# design.net
KiCad netlist of a schematic drawn in Altium Designer
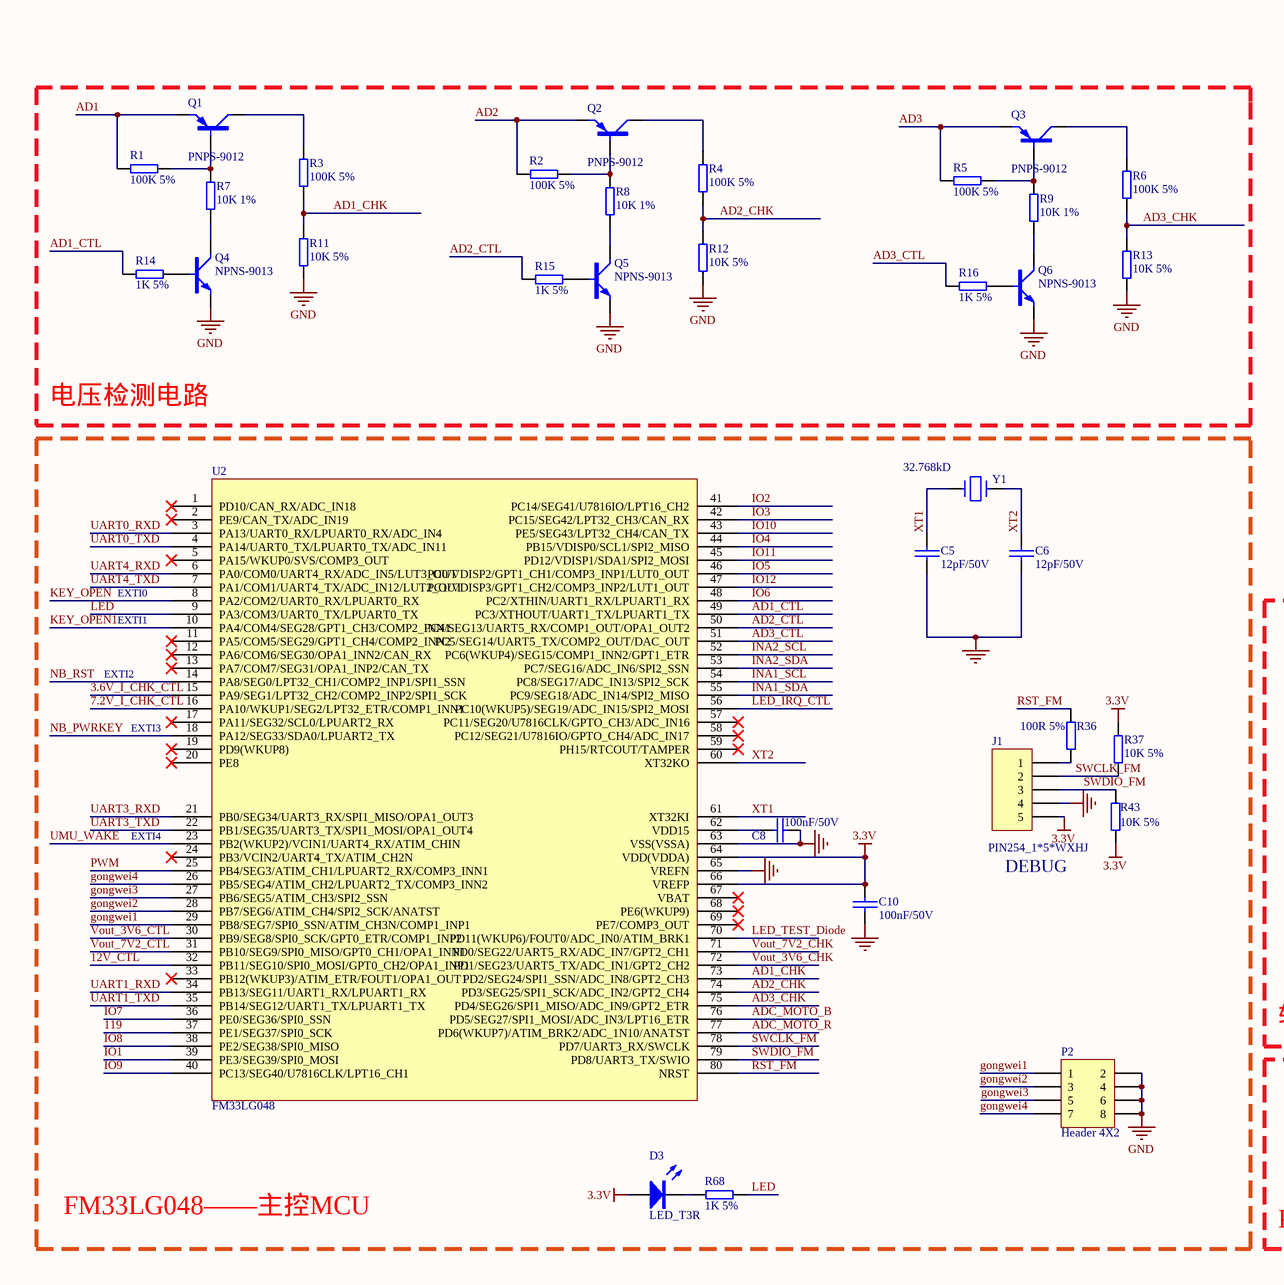
[diagram p0: 主控.SchDoc, left]
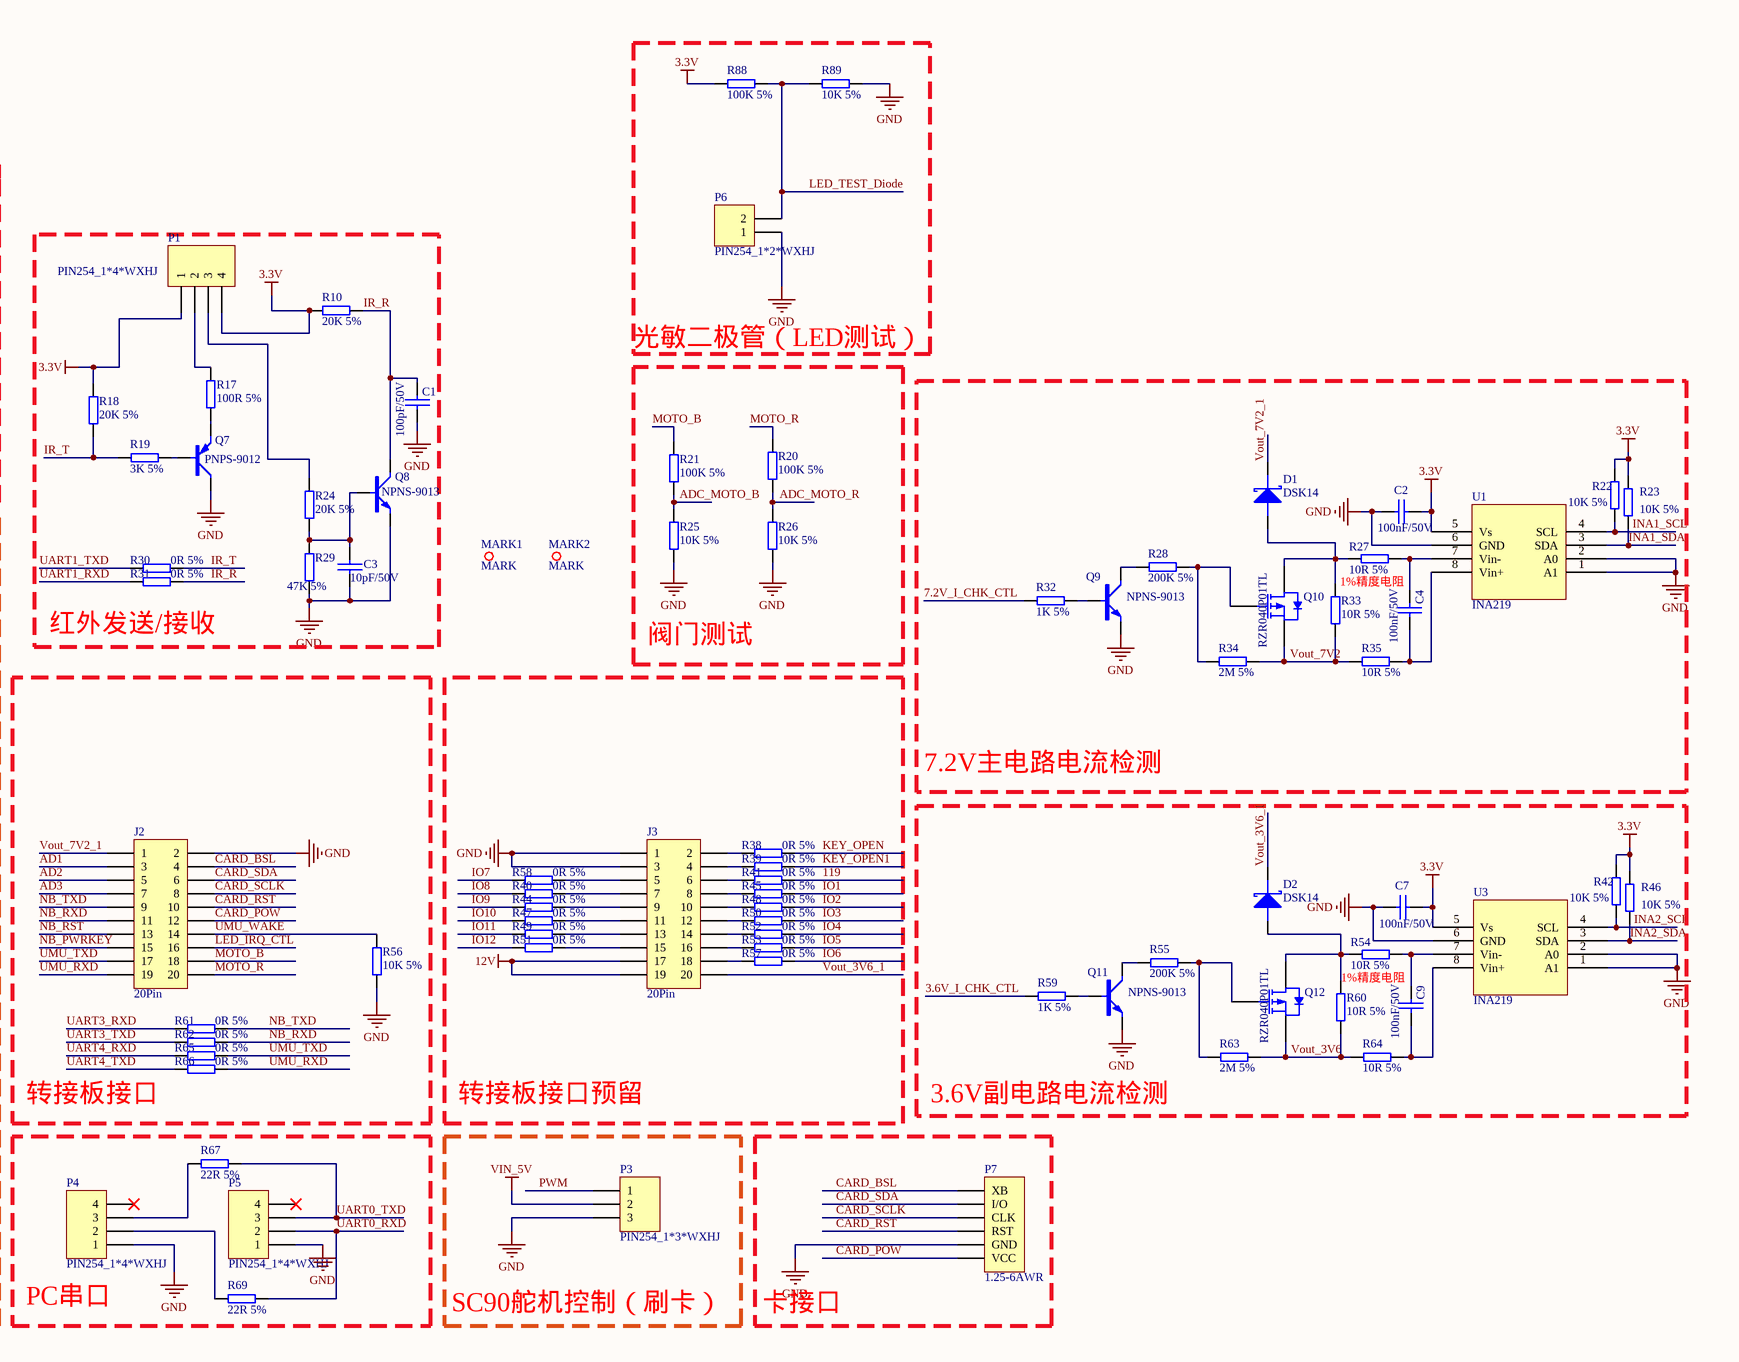
[diagram p1: 主控.SchDoc, right]

(export (version "E")
  (design (tool "Eeschema 10.0.6"))
  (components
    (comp (ref "C1")
      (value "100pF/50V")
      (footprint "CAP0603")
      (description "101pf,50 V,±5%,0603,国巨,CC0603JRNP09BN101")
      (fields (field (name "PART NUMBER") "101020103-0010"))
      (libsource (lib "Database_Libs2") (part "CC03JPO9_101P"))
    )
    (comp (ref "C2")
      (value "100nF/50V")
      (footprint "CAP0603")
      (description "104pF,50 V,±10%,0603,国巨,CC0603KRX7R9BB104")
      (fields (field (name "PART NUMBER") "101020103-0021"))
      (libsource (lib "Database_Libs2") (part "CC03K7R9_100N"))
    )
    (comp (ref "C3")
      (value "10pF/50V")
      (footprint "CAP0603")
      (description "10pF,50 V,±5%,0603,X7R,国巨,CC0603JRNPO9BN100")
      (fields (field (name "PART NUMBER") "101020103-0014"))
      (libsource (lib "Database_Libs2") (part "CC03JPO9_10P"))
    )
    (comp (ref "C4")
      (value "100nF/50V")
      (footprint "CAP0603")
      (description "104pF,50 V,±10%,0603,国巨,CC0603KRX7R9BB104")
      (fields (field (name "PART NUMBER") "101020103-0021"))
      (libsource (lib "Database_Libs2") (part "CC03K7R9_100N"))
    )
    (comp (ref "C5")
      (value "12pF/50V")
      (footprint "CAP0603")
      (description "12P,50 V,±5%,0603,国巨,CC0603JRNPO9BN12")
      (fields (field (name "PART NUMBER") "101020103-0005"))
      (libsource (lib "Database_Libs2") (part "CC03JPO9_12P"))
    )
    (comp (ref "C6")
      (value "12pF/50V")
      (footprint "CAP0603")
      (description "12P,50 V,±5%,0603,国巨,CC0603JRNPO9BN12")
      (fields (field (name "PART NUMBER") "101020103-0005"))
      (libsource (lib "Database_Libs2") (part "CC03JPO9_12P"))
    )
    (comp (ref "C7")
      (value "100nF/50V")
      (footprint "CAP0603")
      (description "104pF,50 V,±10%,0603,国巨,CC0603KRX7R9BB104")
      (fields (field (name "PART NUMBER") "101020103-0021"))
      (libsource (lib "Database_Libs2") (part "CC03K7R9_100N"))
    )
    (comp (ref "C8")
      (value "100nF/50V")
      (footprint "CAP0603")
      (description "104pF,50 V,±10%,0603,国巨,CC0603KRX7R9BB104")
      (fields (field (name "PART NUMBER") "101020103-0021"))
      (libsource (lib "Database_Libs2") (part "CC03K7R9_100N"))
    )
    (comp (ref "C9")
      (value "100nF/50V")
      (footprint "CAP0603")
      (description "104pF,50 V,±10%,0603,国巨,CC0603KRX7R9BB104")
      (fields (field (name "PART NUMBER") "101020103-0021"))
      (libsource (lib "Database_Libs2") (part "CC03K7R9_100N"))
    )
    (comp (ref "C10")
      (value "100nF/50V")
      (footprint "CAP0603")
      (description "104pF,50 V,±10%,0603,国巨,CC0603KRX7R9BB104")
      (fields (field (name "PART NUMBER") "101020103-0021"))
      (libsource (lib "Database_Libs2") (part "CC03K7R9_100N"))
    )
    (comp (ref "D1")
      (value "DSK14")
      (footprint "SOD-123FL")
      (description "DSK14,SOD-123FL,1 A,40 V,28 V,台湾强茂集团苏州群鑫电子,DSK14")
      (fields (field (name "PART NUMBER") "101040101-0043"))
      (libsource (lib "Database_Libs2") (part "02_DSK14"))
    )
    (comp (ref "D2")
      (value "DSK14")
      (footprint "SOD-123FL")
      (description "DSK14,SOD-123FL,1 A,40 V,28 V,台湾强茂集团苏州群鑫电子,DSK14")
      (fields (field (name "PART NUMBER") "101040101-0043"))
      (libsource (lib "Database_Libs2") (part "02_DSK14"))
    )
    (comp (ref "D3")
      (value "LED_T3R")
      (footprint "LED2_300")
      (description "圆形插件,3mm 圆形,插件,红光,湖北匡通电子有限公司,3BB4HC")
      (fields (field (name "PART NUMBER") "101040102-0001"))
      (libsource (lib "Database_Libs2") (part "01-LED_T3R"))
    )
    (comp (ref "J1")
      (value "PIN254_1*5*WXHJ")
      (footprint "PIN254_1*5*1100S")
      (description "1*5 ，Φ1.0 ，2.54mm，直脚,无需焊接器件")
      (fields (field (name "PART NUMBER") "AD_WXHJ_PinHeader_02"))
      (libsource (lib "Database_Libs2") (part "PIN254_1*5*1100S"))
    )
    (comp (ref "J2")
      (value "20Pin")
      (footprint "DC254_2*10")
      (description "DC2 2.54mm 2x10pin,2.54mm间距，2x10pin，32×8.55×27.5mm,母头,双排,双排牛角座")
      (fields (field (name "PART NUMBER") "1010902-0139"))
      (libsource (lib "转接板封装") (part "20Pin"))
    )
    (comp (ref "J3")
      (value "20Pin")
      (footprint "DC254_2*10")
      (description "DC2 2.54mm 2x10pin,2.54mm间距，2x10pin，32×8.55×27.5mm,母头,双排,双排牛角座")
      (fields (field (name "PART NUMBER") "1010902-0139"))
      (libsource (lib "转接板封装") (part "20Pin"))
    )
    (comp (ref "MARK1")
      (value "MARK")
      (footprint "MARK")
      (description "MARK点")
      (fields (field (name "PART NUMBER") "AD_WXHJ_MARK_01"))
      (libsource (lib "转接板封装") (part "MARK"))
    )
    (comp (ref "MARK2")
      (value "MARK")
      (footprint "MARK")
      (description "MARK点")
      (fields (field (name "PART NUMBER") "AD_WXHJ_MARK_01"))
      (libsource (lib "转接板封装") (part "MARK"))
    )
    (comp (ref "P1")
      (value "PIN254_1*4*WXHJ")
      (footprint "PIN254_1*4*1100S")
      (description "1*4 ，Φ1.0 ，2.54mm，直脚,无需焊接器件")
      (fields (field (name "PART NUMBER") "AD_WXHJ_PinHeader_01"))
      (libsource (lib "") (part "PIN254_1*4*1100S_1"))
    )
    (comp (ref "P2")
      (value "Header 4X2")
      (footprint "HDR2X4")
      (description "Header, 4-Pin, Dual row")
      (libsource (lib "CBB_Lib_SCH") (part "Header 4X2"))
    )
    (comp (ref "P3")
      (value "PIN254_1*3*WXHJ")
      (footprint "PIN254_1*3*1100S")
      (description "1*3 ，Φ1.0 ，2.54mm，直脚,无需焊接器件")
      (fields (field (name "PART NUMBER") "AD_WXHJ_PinHeader_01"))
      (libsource (lib "模拟计量") (part "PIN254_1*3*1100S"))
    )
    (comp (ref "P4")
      (value "PIN254_1*4*WXHJ")
      (footprint "PIN254_1*4*1100S")
      (description "1*4 ，Φ1.0 ，2.54mm，直脚,无需焊接器件")
      (fields (field (name "PART NUMBER") "AD_WXHJ_PinHeader_01"))
      (libsource (lib "Database_Libs2") (part "PIN254_1*4*1100S"))
    )
    (comp (ref "P5")
      (value "PIN254_1*4*WXHJ")
      (footprint "PIN254_1*4*1100S")
      (description "1*4 ，Φ1.0 ，2.54mm，直脚,无需焊接器件")
      (fields (field (name "PART NUMBER") "AD_WXHJ_PinHeader_01"))
      (libsource (lib "Database_Libs2") (part "PIN254_1*4*1100S"))
    )
    (comp (ref "P6")
      (value "PIN254_1*2*WXHJ")
      (footprint "PIN254_1*2*1100S")
      (description "1*2 ，Φ1.0 ，2.54mm，直脚,无需焊接器件")
      (fields (field (name "PART NUMBER") "AD_WXHJ_PinHeader_01"))
      (libsource (lib "转接板封装") (part "PIN254_1*2*1100S"))
    )
    (comp (ref "P7")
      (value "1.25-6AWR")
      (footprint "SMT-1.25-6")
      (description "1.25-6AWR 卷,6针1.25mm,母头,单排,贴片卧式")
      (fields (field (name "PART NUMBER") "1010902-0121"))
      (libsource (lib "Database_Libs2") (part "CARD1608"))
    )
    (comp (ref "Q1")
      (value "PNPS-9012")
      (footprint "SOT-23")
      (description "9012,PNP,SOT-23,JCET;长电,S9012")
      (fields (field (name "PART NUMBER") "101040201-0001"))
      (libsource (lib "Database_Libs2") (part "03_PNPS-9012"))
    )
    (comp (ref "Q2")
      (value "PNPS-9012")
      (footprint "SOT-23")
      (description "9012,PNP,SOT-23,JCET;长电,S9012")
      (fields (field (name "PART NUMBER") "101040201-0001"))
      (libsource (lib "Database_Libs2") (part "03_PNPS-9012"))
    )
    (comp (ref "Q3")
      (value "PNPS-9012")
      (footprint "SOT-23")
      (description "9012,PNP,SOT-23,JCET;长电,S9012")
      (fields (field (name "PART NUMBER") "101040201-0001"))
      (libsource (lib "Database_Libs2") (part "03_PNPS-9012"))
    )
    (comp (ref "Q4")
      (value "NPNS-9013")
      (footprint "SOT-23")
      (description "9013,NPN,SOT-23,长电,S9013")
      (fields (field (name "PART NUMBER") "101040201-0002"))
      (libsource (lib "Database_Libs2") (part "03_NPNS-9013"))
    )
    (comp (ref "Q5")
      (value "NPNS-9013")
      (footprint "SOT-23")
      (description "9013,NPN,SOT-23,长电,S9013")
      (fields (field (name "PART NUMBER") "101040201-0002"))
      (libsource (lib "Database_Libs2") (part "03_NPNS-9013"))
    )
    (comp (ref "Q6")
      (value "NPNS-9013")
      (footprint "SOT-23")
      (description "9013,NPN,SOT-23,长电,S9013")
      (fields (field (name "PART NUMBER") "101040201-0002"))
      (libsource (lib "Database_Libs2") (part "03_NPNS-9013"))
    )
    (comp (ref "Q7")
      (value "PNPS-9012")
      (footprint "SOT-23")
      (description "9012,PNP,SOT-23,JCET;长电,S9012")
      (fields (field (name "PART NUMBER") "101040201-0001"))
      (libsource (lib "Database_Libs2") (part "03_PNPS-9012"))
    )
    (comp (ref "Q8")
      (value "NPNS-9013")
      (footprint "SOT-23")
      (description "9013,NPN,SOT-23,长电,S9013")
      (fields (field (name "PART NUMBER") "101040201-0002"))
      (libsource (lib "Database_Libs2") (part "03_NPNS-9013"))
    )
    (comp (ref "Q9")
      (value "NPNS-9013")
      (footprint "SOT-23")
      (description "9013,NPN,SOT-23,长电,S9013")
      (fields (field (name "PART NUMBER") "101040201-0002"))
      (libsource (lib "Database_Libs2") (part "03_NPNS-9013"))
    )
    (comp (ref "Q10")
      (value "RZR040P01TL")
      (footprint "SOT-23")
      (description "RZR040P01TL；1.5v导通,P-MOS,SOT-23,罗姆,RZR040P01TL")
      (fields (field (name "PART NUMBER") "101040201-0010"))
      (libsource (lib "Database_Libs2") (part "03_P-RZR040P01TL"))
    )
    (comp (ref "Q11")
      (value "NPNS-9013")
      (footprint "SOT-23")
      (description "9013,NPN,SOT-23,长电,S9013")
      (fields (field (name "PART NUMBER") "101040201-0002"))
      (libsource (lib "Database_Libs2") (part "03_NPNS-9013"))
    )
    (comp (ref "Q12")
      (value "RZR040P01TL")
      (footprint "SOT-23")
      (description "RZR040P01TL；1.5v导通,P-MOS,SOT-23,罗姆,RZR040P01TL")
      (fields (field (name "PART NUMBER") "101040201-0010"))
      (libsource (lib "Database_Libs2") (part "03_P-RZR040P01TL"))
    )
    (comp (ref "R1")
      (value "100K 5%")
      (footprint "RES0603")
      (description "国巨,±5%,0603,,155 ℃,-55 ℃,RC0603JR-07100KL,无铅,100 ppm/℃,1/10W,,100K")
      (fields (field (name "PART NUMBER") "101010103-0005"))
      (libsource (lib "Database_Libs2") (part "RC03J_100K"))
    )
    (comp (ref "R2")
      (value "100K 5%")
      (footprint "RES0603")
      (description "国巨,±5%,0603,,155 ℃,-55 ℃,RC0603JR-07100KL,无铅,100 ppm/℃,1/10W,,100K")
      (fields (field (name "PART NUMBER") "101010103-0005"))
      (libsource (lib "Database_Libs2") (part "RC03J_100K"))
    )
    (comp (ref "R3")
      (value "100K 5%")
      (footprint "RES0603")
      (description "国巨,±5%,0603,,155 ℃,-55 ℃,RC0603JR-07100KL,无铅,100 ppm/℃,1/10W,,100K")
      (fields (field (name "PART NUMBER") "101010103-0005"))
      (libsource (lib "Database_Libs2") (part "RC03J_100K"))
    )
    (comp (ref "R4")
      (value "100K 5%")
      (footprint "RES0603")
      (description "国巨,±5%,0603,,155 ℃,-55 ℃,RC0603JR-07100KL,无铅,100 ppm/℃,1/10W,,100K")
      (fields (field (name "PART NUMBER") "101010103-0005"))
      (libsource (lib "Database_Libs2") (part "RC03J_100K"))
    )
    (comp (ref "R5")
      (value "100K 5%")
      (footprint "RES0603")
      (description "国巨,±5%,0603,,155 ℃,-55 ℃,RC0603JR-07100KL,无铅,100 ppm/℃,1/10W,,100K")
      (fields (field (name "PART NUMBER") "101010103-0005"))
      (libsource (lib "Database_Libs2") (part "RC03J_100K"))
    )
    (comp (ref "R6")
      (value "100K 5%")
      (footprint "RES0603")
      (description "国巨,±5%,0603,,155 ℃,-55 ℃,RC0603JR-07100KL,无铅,100 ppm/℃,1/10W,,100K")
      (fields (field (name "PART NUMBER") "101010103-0005"))
      (libsource (lib "Database_Libs2") (part "RC03J_100K"))
    )
    (comp (ref "R7")
      (value "10K 1%")
      (footprint "RES0603")
      (description "10K±1%,1/10W,0603")
      (fields (field (name "PART NUMBER") "101010103-0052"))
      (libsource (lib "Database_Libs2") (part "RC03J_10K"))
    )
    (comp (ref "R8")
      (value "10K 1%")
      (footprint "RES0603")
      (description "10K±1%,1/10W,0603")
      (fields (field (name "PART NUMBER") "101010103-0052"))
      (libsource (lib "Database_Libs2") (part "RC03J_10K"))
    )
    (comp (ref "R9")
      (value "10K 1%")
      (footprint "RES0603")
      (description "10K±1%,1/10W,0603")
      (fields (field (name "PART NUMBER") "101010103-0052"))
      (libsource (lib "Database_Libs2") (part "RC03J_10K"))
    )
    (comp (ref "R10")
      (value "20K 5%")
      (footprint "RES0603")
      (description "国巨,±5%,0603,,155 ℃,-55 ℃,RC0603JR-0720KL,无铅,200 ppm/℃,1/10W,,20K")
      (fields (field (name "PART NUMBER") "101010103-0004"))
      (libsource (lib "Database_Libs2") (part "RC03J_20K"))
    )
    (comp (ref "R11")
      (value "10K 5%")
      (footprint "RES0603")
      (description "国巨,±5%,0603,,155 ℃,-55 ℃,RC0603JR-0710KL,无铅,200 ppm/℃,1/10W,,10K")
      (fields (field (name "PART NUMBER") "101010103-0003"))
      (libsource (lib "Database_Libs2") (part "RC03J_10K"))
    )
    (comp (ref "R12")
      (value "10K 5%")
      (footprint "RES0603")
      (description "国巨,±5%,0603,,155 ℃,-55 ℃,RC0603JR-0710KL,无铅,200 ppm/℃,1/10W,,10K")
      (fields (field (name "PART NUMBER") "101010103-0003"))
      (libsource (lib "Database_Libs2") (part "RC03J_10K"))
    )
    (comp (ref "R13")
      (value "10K 5%")
      (footprint "RES0603")
      (description "国巨,±5%,0603,,155 ℃,-55 ℃,RC0603JR-0710KL,无铅,200 ppm/℃,1/10W,,10K")
      (fields (field (name "PART NUMBER") "101010103-0003"))
      (libsource (lib "Database_Libs2") (part "RC03J_10K"))
    )
    (comp (ref "R14")
      (value "1K 5%")
      (footprint "RES0603")
      (description "1K,±5%,1/10W,0603,国巨,RC0603JR-071KL")
      (fields (field (name "PART NUMBER") "101010103-0008"))
      (libsource (lib "Database_Libs2") (part "RC03J_1K"))
    )
    (comp (ref "R15")
      (value "1K 5%")
      (footprint "RES0603")
      (description "1K,±5%,1/10W,0603,国巨,RC0603JR-071KL")
      (fields (field (name "PART NUMBER") "101010103-0008"))
      (libsource (lib "Database_Libs2") (part "RC03J_1K"))
    )
    (comp (ref "R16")
      (value "1K 5%")
      (footprint "RES0603")
      (description "1K,±5%,1/10W,0603,国巨,RC0603JR-071KL")
      (fields (field (name "PART NUMBER") "101010103-0008"))
      (libsource (lib "Database_Libs2") (part "RC03J_1K"))
    )
    (comp (ref "R17")
      (value "100R 5%")
      (footprint "RES0603")
      (description "100R,±5%,1/10W,0603,国巨,RC0603JR-07100RL")
      (fields (field (name "PART NUMBER") "101010103-0022"))
      (libsource (lib "Database_Libs2") (part "RC03J_100R"))
    )
    (comp (ref "R18")
      (value "20K 5%")
      (footprint "RES0603")
      (description "国巨,±5%,0603,,155 ℃,-55 ℃,RC0603JR-0720KL,无铅,200 ppm/℃,1/10W,,20K")
      (fields (field (name "PART NUMBER") "101010103-0004"))
      (libsource (lib "Database_Libs2") (part "RC03J_20K"))
    )
    (comp (ref "R19")
      (value "3K 5%")
      (footprint "RES0603")
      (description "国巨,±5%,0603,,155 ℃,-55 ℃,RC0603JR-073KL,无铅,100 ppm/℃,1/10W,,3K")
      (fields (field (name "PART NUMBER") "101010103-0006"))
      (libsource (lib "Database_Libs2") (part "RC03J_3K"))
    )
    (comp (ref "R20")
      (value "100K 5%")
      (footprint "RES0603")
      (description "100K±5%,1/10W,0603")
      (fields (field (name "PART NUMBER") "101010103-0005"))
      (libsource (lib "Database_Libs1") (part "RC03JF_100K"))
    )
    (comp (ref "R21")
      (value "100K 5%")
      (footprint "RES0603")
      (description "100K±5%,1/10W,0603")
      (fields (field (name "PART NUMBER") "101010103-0005"))
      (libsource (lib "Database_Libs1") (part "RC03JF_100K"))
    )
    (comp (ref "R22")
      (value "10K 5%")
      (footprint "RES0603")
      (description "国巨,±5%,0603,,155 ℃,-55 ℃,RC0603JR-0710KL,无铅,200 ppm/℃,1/10W,,10K")
      (fields (field (name "PART NUMBER") "101010103-0003"))
      (libsource (lib "Database_Libs2") (part "RC03J_10K"))
    )
    (comp (ref "R23")
      (value "10K 5%")
      (footprint "RES0603")
      (description "国巨,±5%,0603,,155 ℃,-55 ℃,RC0603JR-0710KL,无铅,200 ppm/℃,1/10W,,10K")
      (fields (field (name "PART NUMBER") "101010103-0003"))
      (libsource (lib "Database_Libs2") (part "RC03J_10K"))
    )
    (comp (ref "R24")
      (value "20K 5%")
      (footprint "RES0603")
      (description "国巨,±5%,0603,,155 ℃,-55 ℃,RC0603JR-0720KL,无铅,200 ppm/℃,1/10W,,20K")
      (fields (field (name "PART NUMBER") "101010103-0004"))
      (libsource (lib "Database_Libs2") (part "RC03J_20K"))
    )
    (comp (ref "R25")
      (value "10K 5%")
      (footprint "RES0603")
      (description "国巨,±5%,0603,,155 ℃,-55 ℃,RC0603JR-0710KL,无铅,200 ppm/℃,1/10W,,10K")
      (fields (field (name "PART NUMBER") "101010103-0003"))
      (libsource (lib "Database_Libs2") (part "RC03J_10K"))
    )
    (comp (ref "R26")
      (value "10K 5%")
      (footprint "RES0603")
      (description "国巨,±5%,0603,,155 ℃,-55 ℃,RC0603JR-0710KL,无铅,200 ppm/℃,1/10W,,10K")
      (fields (field (name "PART NUMBER") "101010103-0003"))
      (libsource (lib "Database_Libs2") (part "RC03J_10K"))
    )
    (comp (ref "R27")
      (value "10R 5%")
      (footprint "RES0603")
      (description "10R,±5%,1/10W,0603,国巨,RC0603JR-0710RL")
      (fields (field (name "PART NUMBER") "101010103-0017"))
      (libsource (lib "Database_Libs2") (part "RC03J_10R"))
    )
    (comp (ref "R28")
      (value "200K 5%")
      (footprint "RES0603")
      (description "200K,±5%,1/10W,0603,国巨,RC0603JR-07200KL")
      (fields (field (name "PART NUMBER") "101010103-0034"))
      (libsource (lib "Database_Libs2") (part "RC03J_200K"))
    )
    (comp (ref "R29")
      (value "47K 5%")
      (footprint "RES0603")
      (description "47K,±5%,1/10W,0603,国巨,RC0603JR-0747KL")
      (fields (field (name "PART NUMBER") "101010103-0012"))
      (libsource (lib "Database_Libs2") (part "RC03J_47K"))
    )
    (comp (ref "R30")
      (value "0R 5%")
      (footprint "RES0603")
      (description "国巨,±5%,0603,,155 ℃,-55 ℃,RC0603J2-070RL,无铅,200 ppm/℃,1/10W,,0R")
      (fields (field (name "PART NUMBER") "101010103-0001"))
      (libsource (lib "Database_Libs2") (part "RC03J_0R"))
    )
    (comp (ref "R31")
      (value "0R 5%")
      (footprint "RES0603")
      (description "国巨,±5%,0603,,155 ℃,-55 ℃,RC0603J2-070RL,无铅,200 ppm/℃,1/10W,,0R")
      (fields (field (name "PART NUMBER") "101010103-0001"))
      (libsource (lib "Database_Libs2") (part "RC03J_0R"))
    )
    (comp (ref "R32")
      (value "1K 5%")
      (footprint "RES0603")
      (description "1K,±5%,1/10W,0603,国巨,RC0603JR-071KL")
      (fields (field (name "PART NUMBER") "101010103-0008"))
      (libsource (lib "Database_Libs2") (part "RC03J_1K"))
    )
    (comp (ref "R33")
      (value "10R 5%")
      (footprint "RES0603")
      (description "10R,±5%,1/10W,0603,国巨,RC0603JR-0710RL")
      (fields (field (name "PART NUMBER") "101010103-0017"))
      (libsource (lib "Database_Libs2") (part "RC03J_10R"))
    )
    (comp (ref "R34")
      (value "2M 5%")
      (footprint "RES0603")
      (description "国巨,±5%,0603,,155 ℃,-55 ℃,RC0603JR-072ML,含铅,100 ppm/℃,1/10W,,2M")
      (fields (field (name "PART NUMBER") "101010103-0025"))
      (libsource (lib "Database_Libs2") (part "RC03J_2M"))
    )
    (comp (ref "R35")
      (value "10R 5%")
      (footprint "RES0603")
      (description "10R,±5%,1/10W,0603,国巨,RC0603JR-0710RL")
      (fields (field (name "PART NUMBER") "101010103-0017"))
      (libsource (lib "Database_Libs2") (part "RC03J_10R"))
    )
    (comp (ref "R36")
      (value "100R 5%")
      (footprint "RES0603")
      (description "100R,±5%,1/10W,0603,国巨,RC0603JR-07100RL")
      (fields (field (name "PART NUMBER") "101010103-0022"))
      (libsource (lib "Database_Libs2") (part "RC03J_100R"))
    )
    (comp (ref "R37")
      (value "10K 5%")
      (footprint "RES0603")
      (description "国巨,±5%,0603,,155 ℃,-55 ℃,RC0603JR-0710KL,无铅,200 ppm/℃,1/10W,,10K")
      (fields (field (name "PART NUMBER") "101010103-0003"))
      (libsource (lib "Database_Libs2") (part "RC03J_10K"))
    )
    (comp (ref "R38")
      (value "0R 5%")
      (footprint "RES0603")
      (description "国巨,±5%,0603,,155 ℃,-55 ℃,RC0603J2-070RL,无铅,200 ppm/℃,1/10W,,0R")
      (fields (field (name "PART NUMBER") "101010103-0001"))
      (libsource (lib "Database_Libs2") (part "RC03J_0R"))
    )
    (comp (ref "R39")
      (value "0R 5%")
      (footprint "RES0603")
      (description "国巨,±5%,0603,,155 ℃,-55 ℃,RC0603J2-070RL,无铅,200 ppm/℃,1/10W,,0R")
      (fields (field (name "PART NUMBER") "101010103-0001"))
      (libsource (lib "Database_Libs2") (part "RC03J_0R"))
    )
    (comp (ref "R40")
      (value "0R 5%")
      (footprint "RES0603")
      (description "国巨,±5%,0603,,155 ℃,-55 ℃,RC0603J2-070RL,无铅,200 ppm/℃,1/10W,,0R")
      (fields (field (name "PART NUMBER") "101010103-0001"))
      (libsource (lib "Database_Libs2") (part "RC03J_0R"))
    )
    (comp (ref "R41")
      (value "0R 5%")
      (footprint "RES0603")
      (description "国巨,±5%,0603,,155 ℃,-55 ℃,RC0603J2-070RL,无铅,200 ppm/℃,1/10W,,0R")
      (fields (field (name "PART NUMBER") "101010103-0001"))
      (libsource (lib "Database_Libs2") (part "RC03J_0R"))
    )
    (comp (ref "R42")
      (value "10K 5%")
      (footprint "RES0603")
      (description "国巨,±5%,0603,,155 ℃,-55 ℃,RC0603JR-0710KL,无铅,200 ppm/℃,1/10W,,10K")
      (fields (field (name "PART NUMBER") "101010103-0003"))
      (libsource (lib "Database_Libs2") (part "RC03J_10K"))
    )
    (comp (ref "R43")
      (value "10K 5%")
      (footprint "RES0603")
      (description "国巨,±5%,0603,,155 ℃,-55 ℃,RC0603JR-0710KL,无铅,200 ppm/℃,1/10W,,10K")
      (fields (field (name "PART NUMBER") "101010103-0003"))
      (libsource (lib "Database_Libs2") (part "RC03J_10K"))
    )
    (comp (ref "R44")
      (value "0R 5%")
      (footprint "RES0603")
      (description "国巨,±5%,0603,,155 ℃,-55 ℃,RC0603J2-070RL,无铅,200 ppm/℃,1/10W,,0R")
      (fields (field (name "PART NUMBER") "101010103-0001"))
      (libsource (lib "Database_Libs2") (part "RC03J_0R"))
    )
    (comp (ref "R45")
      (value "0R 5%")
      (footprint "RES0603")
      (description "国巨,±5%,0603,,155 ℃,-55 ℃,RC0603J2-070RL,无铅,200 ppm/℃,1/10W,,0R")
      (fields (field (name "PART NUMBER") "101010103-0001"))
      (libsource (lib "Database_Libs2") (part "RC03J_0R"))
    )
    (comp (ref "R46")
      (value "10K 5%")
      (footprint "RES0603")
      (description "国巨,±5%,0603,,155 ℃,-55 ℃,RC0603JR-0710KL,无铅,200 ppm/℃,1/10W,,10K")
      (fields (field (name "PART NUMBER") "101010103-0003"))
      (libsource (lib "Database_Libs2") (part "RC03J_10K"))
    )
    (comp (ref "R47")
      (value "0R 5%")
      (footprint "RES0603")
      (description "国巨,±5%,0603,,155 ℃,-55 ℃,RC0603J2-070RL,无铅,200 ppm/℃,1/10W,,0R")
      (fields (field (name "PART NUMBER") "101010103-0001"))
      (libsource (lib "Database_Libs2") (part "RC03J_0R"))
    )
    (comp (ref "R48")
      (value "0R 5%")
      (footprint "RES0603")
      (description "国巨,±5%,0603,,155 ℃,-55 ℃,RC0603J2-070RL,无铅,200 ppm/℃,1/10W,,0R")
      (fields (field (name "PART NUMBER") "101010103-0001"))
      (libsource (lib "Database_Libs2") (part "RC03J_0R"))
    )
    (comp (ref "R49")
      (value "0R 5%")
      (footprint "RES0603")
      (description "国巨,±5%,0603,,155 ℃,-55 ℃,RC0603J2-070RL,无铅,200 ppm/℃,1/10W,,0R")
      (fields (field (name "PART NUMBER") "101010103-0001"))
      (libsource (lib "Database_Libs2") (part "RC03J_0R"))
    )
    (comp (ref "R50")
      (value "0R 5%")
      (footprint "RES0603")
      (description "国巨,±5%,0603,,155 ℃,-55 ℃,RC0603J2-070RL,无铅,200 ppm/℃,1/10W,,0R")
      (fields (field (name "PART NUMBER") "101010103-0001"))
      (libsource (lib "Database_Libs2") (part "RC03J_0R"))
    )
    (comp (ref "R51")
      (value "0R 5%")
      (footprint "RES0603")
      (description "国巨,±5%,0603,,155 ℃,-55 ℃,RC0603J2-070RL,无铅,200 ppm/℃,1/10W,,0R")
      (fields (field (name "PART NUMBER") "101010103-0001"))
      (libsource (lib "Database_Libs2") (part "RC03J_0R"))
    )
    (comp (ref "R52")
      (value "0R 5%")
      (footprint "RES0603")
      (description "国巨,±5%,0603,,155 ℃,-55 ℃,RC0603J2-070RL,无铅,200 ppm/℃,1/10W,,0R")
      (fields (field (name "PART NUMBER") "101010103-0001"))
      (libsource (lib "Database_Libs2") (part "RC03J_0R"))
    )
    (comp (ref "R53")
      (value "0R 5%")
      (footprint "RES0603")
      (description "国巨,±5%,0603,,155 ℃,-55 ℃,RC0603J2-070RL,无铅,200 ppm/℃,1/10W,,0R")
      (fields (field (name "PART NUMBER") "101010103-0001"))
      (libsource (lib "Database_Libs2") (part "RC03J_0R"))
    )
    (comp (ref "R54")
      (value "10R 5%")
      (footprint "RES0603")
      (description "10R,±5%,1/10W,0603,国巨,RC0603JR-0710RL")
      (fields (field (name "PART NUMBER") "101010103-0017"))
      (libsource (lib "Database_Libs2") (part "RC03J_10R"))
    )
    (comp (ref "R55")
      (value "200K 5%")
      (footprint "RES0603")
      (description "200K,±5%,1/10W,0603,国巨,RC0603JR-07200KL")
      (fields (field (name "PART NUMBER") "101010103-0034"))
      (libsource (lib "Database_Libs2") (part "RC03J_200K"))
    )
    (comp (ref "R56")
      (value "10K 5%")
      (footprint "RES0603")
      (description "国巨,±5%,0603,,155 ℃,-55 ℃,RC0603JR-0710KL,无铅,200 ppm/℃,1/10W,,10K")
      (fields (field (name "PART NUMBER") "101010103-0003"))
      (libsource (lib "Database_Libs2") (part "RC03J_10K"))
    )
    (comp (ref "R57")
      (value "0R 5%")
      (footprint "RES0603")
      (description "国巨,±5%,0603,,155 ℃,-55 ℃,RC0603J2-070RL,无铅,200 ppm/℃,1/10W,,0R")
      (fields (field (name "PART NUMBER") "101010103-0001"))
      (libsource (lib "Database_Libs2") (part "RC03J_0R"))
    )
    (comp (ref "R58")
      (value "0R 5%")
      (footprint "RES0603")
      (description "国巨,±5%,0603,,155 ℃,-55 ℃,RC0603J2-070RL,无铅,200 ppm/℃,1/10W,,0R")
      (fields (field (name "PART NUMBER") "101010103-0001"))
      (libsource (lib "Database_Libs2") (part "RC03J_0R"))
    )
    (comp (ref "R59")
      (value "1K 5%")
      (footprint "RES0603")
      (description "1K,±5%,1/10W,0603,国巨,RC0603JR-071KL")
      (fields (field (name "PART NUMBER") "101010103-0008"))
      (libsource (lib "Database_Libs2") (part "RC03J_1K"))
    )
    (comp (ref "R60")
      (value "10R 5%")
      (footprint "RES0603")
      (description "10R,±5%,1/10W,0603,国巨,RC0603JR-0710RL")
      (fields (field (name "PART NUMBER") "101010103-0017"))
      (libsource (lib "Database_Libs2") (part "RC03J_10R"))
    )
    (comp (ref "R61")
      (value "0R 5%")
      (footprint "RES0603")
      (description "国巨,±5%,0603,,155 ℃,-55 ℃,RC0603J2-070RL,无铅,200 ppm/℃,1/10W,,0R")
      (fields (field (name "PART NUMBER") "101010103-0001"))
      (libsource (lib "Database_Libs2") (part "RC03J_0R"))
    )
    (comp (ref "R62")
      (value "0R 5%")
      (footprint "RES0603")
      (description "国巨,±5%,0603,,155 ℃,-55 ℃,RC0603J2-070RL,无铅,200 ppm/℃,1/10W,,0R")
      (fields (field (name "PART NUMBER") "101010103-0001"))
      (libsource (lib "Database_Libs2") (part "RC03J_0R"))
    )
    (comp (ref "R63")
      (value "2M 5%")
      (footprint "RES0603")
      (description "国巨,±5%,0603,,155 ℃,-55 ℃,RC0603JR-072ML,含铅,100 ppm/℃,1/10W,,2M")
      (fields (field (name "PART NUMBER") "101010103-0025"))
      (libsource (lib "Database_Libs2") (part "RC03J_2M"))
    )
    (comp (ref "R64")
      (value "10R 5%")
      (footprint "RES0603")
      (description "10R,±5%,1/10W,0603,国巨,RC0603JR-0710RL")
      (fields (field (name "PART NUMBER") "101010103-0017"))
      (libsource (lib "Database_Libs2") (part "RC03J_10R"))
    )
    (comp (ref "R65")
      (value "0R 5%")
      (footprint "RES0603")
      (description "国巨,±5%,0603,,155 ℃,-55 ℃,RC0603J2-070RL,无铅,200 ppm/℃,1/10W,,0R")
      (fields (field (name "PART NUMBER") "101010103-0001"))
      (libsource (lib "Database_Libs2") (part "RC03J_0R"))
    )
    (comp (ref "R66")
      (value "0R 5%")
      (footprint "RES0603")
      (description "国巨,±5%,0603,,155 ℃,-55 ℃,RC0603J2-070RL,无铅,200 ppm/℃,1/10W,,0R")
      (fields (field (name "PART NUMBER") "101010103-0001"))
      (libsource (lib "Database_Libs2") (part "RC03J_0R"))
    )
    (comp (ref "R67")
      (value "22R 5%")
      (footprint "RES0603")
      (description "国巨,±5%,0603,,155 ℃,-55 ℃,RC0603JR-0722RL,无铅,200 ppm/℃,1/10W,,22欧")
      (fields (field (name "PART NUMBER") "101010103-0009"))
      (libsource (lib "Database_Libs2") (part "RC03J_22R"))
    )
    (comp (ref "R68")
      (value "1K 5%")
      (footprint "RES0603")
      (description "1K,±5%,1/10W,0603,国巨,RC0603JR-071KL")
      (fields (field (name "PART NUMBER") "101010103-0008"))
      (libsource (lib "Database_Libs2") (part "RC03J_1K"))
    )
    (comp (ref "R69")
      (value "22R 5%")
      (footprint "RES0603")
      (description "国巨,±5%,0603,,155 ℃,-55 ℃,RC0603JR-0722RL,无铅,200 ppm/℃,1/10W,,22欧")
      (fields (field (name "PART NUMBER") "101010103-0009"))
      (libsource (lib "Database_Libs2") (part "RC03J_22R"))
    )
    (comp (ref "R88")
      (value "100K 5%")
      (footprint "RES0603")
      (description "国巨,±5%,0603,,155 ℃,-55 ℃,RC0603JR-07100KL,无铅,100 ppm/℃,1/10W,,100K")
      (fields (field (name "PART NUMBER") "101010103-0005"))
      (libsource (lib "Database_Libs2") (part "RC03J_100K"))
    )
    (comp (ref "R89")
      (value "10K 5%")
      (footprint "RES0603")
      (description "国巨,±5%,0603,,155 ℃,-55 ℃,RC0603JR-0710KL,无铅,200 ppm/℃,1/10W,,10K")
      (fields (field (name "PART NUMBER") "101010103-0003"))
      (libsource (lib "转接板封装") (part "RC03J_10K"))
    )
    (comp (ref "U1") (value "INA219") (footprint "SO-8") (libsource (lib "转接板封装") (part "INA219")))
    (comp (ref "U2")
      (value "FM33LG048")
      (footprint "LQFP80")
      (description "101050101-0261")
      (libsource (lib "转接板封装") (part "FM33LG048"))
    )
    (comp (ref "U3") (value "INA219") (footprint "SO-8") (libsource (lib "转接板封装") (part "INA219")))
    (comp (ref "Y1")
      (value "32.768kD")
      (footprint "SMD-3215_2P")
      (fields (field (name "PART NUMBER") "1010601-0020"))
      (libsource (lib "Database_Libs2") (part "04_XTALSG12MD_32.768kD"))
    )
  )
  (nets
    (net (code "1") (name "/3.6V_I_CHK_CTL") (class "Default")
      (node (ref "R59") (pin "2") (pinfunction "2_2") (pintype "passive"))
      (node (ref "U2") (pin "15") (pinfunction "PA9/SEG1/LPT32_CH2/COMP2_INP2/SPI1_SCK_15") (pintype "passive"))
    )
    (net (code "2") (name "/7.2V_I_CHK_CTL") (class "Default")
      (node (ref "R32") (pin "2") (pinfunction "2_2") (pintype "passive"))
      (node (ref "U2") (pin "16") (pinfunction "PA10/WKUP1/SEG2/LPT32_ETR/COMP1_INN1_16") (pintype "passive"))
    )
    (net (code "3") (name "/12V_CTL") (class "Default")
      (node (ref "U2") (pin "32") (pinfunction "PB11/SEG10/SPI0_MOSI/GPT0_CH2/OPA1_INP1_32") (pintype "passive"))
    )
    (net (code "4") (name "/119") (class "Default")
      (node (ref "R41") (pin "2") (pinfunction "2_2") (pintype "passive"))
      (node (ref "U2") (pin "37") (pinfunction "PE1/SEG37/SPI0_SCK_37") (pintype "passive"))
    )
    (net (code "5") (name "/AD1") (class "Default")
      (node (ref "J2") (pin "3") (pinfunction "3_3") (pintype "passive"))
      (node (ref "Q1") (pin "2") (pinfunction "E_2") (pintype "passive"))
      (node (ref "R1") (pin "2") (pinfunction "2_2") (pintype "passive"))
    )
    (net (code "6") (name "/AD1_CHK") (class "Default")
      (node (ref "R11") (pin "1") (pinfunction "1_1") (pintype "passive"))
      (node (ref "R3") (pin "2") (pinfunction "2_2") (pintype "passive"))
      (node (ref "U2") (pin "73") (pinfunction "PD2/SEG24/SPI1_SSN/ADC_IN8/GPT2_CH3_73") (pintype "passive"))
    )
    (net (code "7") (name "/AD1_CTL") (class "Default")
      (node (ref "R14") (pin "1") (pinfunction "1_1") (pintype "passive"))
      (node (ref "U2") (pin "49") (pinfunction "PC3/XTHOUT/UART1_TX/LPUART1_TX_49") (pintype "passive"))
    )
    (net (code "8") (name "/AD2") (class "Default")
      (node (ref "J2") (pin "5") (pinfunction "5_5") (pintype "passive"))
      (node (ref "Q2") (pin "2") (pinfunction "E_2") (pintype "passive"))
      (node (ref "R2") (pin "2") (pinfunction "2_2") (pintype "passive"))
    )
    (net (code "9") (name "/AD2_CHK") (class "Default")
      (node (ref "R12") (pin "1") (pinfunction "1_1") (pintype "passive"))
      (node (ref "R4") (pin "2") (pinfunction "2_2") (pintype "passive"))
      (node (ref "U2") (pin "74") (pinfunction "PD3/SEG25/SPI1_SCK/ADC_IN2/GPT2_CH4_74") (pintype "passive"))
    )
    (net (code "10") (name "/AD2_CTL") (class "Default")
      (node (ref "R15") (pin "1") (pinfunction "1_1") (pintype "passive"))
      (node (ref "U2") (pin "50") (pinfunction "PC4/SEG13/UART5_RX/COMP1_OUT/OPA1_OUT2_50") (pintype "passive"))
    )
    (net (code "11") (name "/AD3") (class "Default")
      (node (ref "J2") (pin "7") (pinfunction "7_7") (pintype "passive"))
      (node (ref "Q3") (pin "2") (pinfunction "E_2") (pintype "passive"))
      (node (ref "R5") (pin "2") (pinfunction "2_2") (pintype "passive"))
    )
    (net (code "12") (name "/AD3_CHK") (class "Default")
      (node (ref "R13") (pin "1") (pinfunction "1_1") (pintype "passive"))
      (node (ref "R6") (pin "2") (pinfunction "2_2") (pintype "passive"))
      (node (ref "U2") (pin "75") (pinfunction "PD4/SEG26/SPI1_MISO/ADC_IN9/GPT2_ETR_75") (pintype "passive"))
    )
    (net (code "13") (name "/AD3_CTL") (class "Default")
      (node (ref "R16") (pin "1") (pinfunction "1_1") (pintype "passive"))
      (node (ref "U2") (pin "51") (pinfunction "PC5/SEG14/UART5_TX/COMP2_OUT/DAC_OUT_51") (pintype "passive"))
    )
    (net (code "14") (name "/ADC_MOTO_B") (class "Default")
      (node (ref "R21") (pin "1") (pinfunction "1_1") (pintype "passive"))
      (node (ref "R25") (pin "2") (pinfunction "2_2") (pintype "passive"))
      (node (ref "U2") (pin "76") (pinfunction "PD5/SEG27/SPI1_MOSI/ADC_IN3/LPT16_ETR_76") (pintype "passive"))
    )
    (net (code "15") (name "/ADC_MOTO_R") (class "Default")
      (node (ref "R20") (pin "1") (pinfunction "1_1") (pintype "passive"))
      (node (ref "R26") (pin "2") (pinfunction "2_2") (pintype "passive"))
      (node (ref "U2") (pin "77") (pinfunction "PD6(WKUP7)/ATIM_BRK2/ADC_1N10/ANATST_77") (pintype "passive"))
    )
    (net (code "16") (name "/CARD_BSL") (class "Default")
      (node (ref "J2") (pin "4") (pinfunction "4_4") (pintype "passive"))
      (node (ref "P7") (pin "1") (pinfunction "XB_1") (pintype "passive"))
    )
    (net (code "17") (name "/CARD_POW") (class "Default")
      (node (ref "J2") (pin "12") (pinfunction "12_12") (pintype "passive"))
      (node (ref "P7") (pin "6") (pinfunction "VCC_6") (pintype "passive"))
    )
    (net (code "18") (name "/CARD_RST") (class "Default")
      (node (ref "J2") (pin "10") (pinfunction "10_10") (pintype "passive"))
      (node (ref "P7") (pin "4") (pinfunction "RST_4") (pintype "passive"))
    )
    (net (code "19") (name "/CARD_SCLK") (class "Default")
      (node (ref "J2") (pin "8") (pinfunction "8_8") (pintype "passive"))
      (node (ref "P7") (pin "3") (pinfunction "CLK_3") (pintype "passive"))
    )
    (net (code "20") (name "/CARD_SDA") (class "Default")
      (node (ref "J2") (pin "6") (pinfunction "6_6") (pintype "passive"))
      (node (ref "P7") (pin "2") (pinfunction "I/O_2") (pintype "passive"))
    )
    (net (code "21") (name "/INA1_SCL") (class "Default")
      (node (ref "R22") (pin "2") (pinfunction "2_2") (pintype "passive"))
      (node (ref "U1") (pin "4") (pinfunction "SCL_4") (pintype "passive"))
      (node (ref "U2") (pin "54") (pinfunction "PC8/SEG17/ADC_IN13/SPI2_SCK_54") (pintype "passive"))
    )
    (net (code "22") (name "/INA1_SDA") (class "Default")
      (node (ref "R23") (pin "2") (pinfunction "2_2") (pintype "passive"))
      (node (ref "U1") (pin "3") (pinfunction "SDA_3") (pintype "passive"))
      (node (ref "U2") (pin "55") (pinfunction "PC9/SEG18/ADC_IN14/SPI2_MISO_55") (pintype "passive"))
    )
    (net (code "23") (name "/INA2_SCL") (class "Default")
      (node (ref "R42") (pin "2") (pinfunction "2_2") (pintype "passive"))
      (node (ref "U2") (pin "52") (pinfunction "PC6(WKUP4)/SEG15/COMP1_INN2/GPT1_ETR_52") (pintype "passive"))
      (node (ref "U3") (pin "4") (pinfunction "SCL_4") (pintype "passive"))
    )
    (net (code "24") (name "/INA2_SDA") (class "Default")
      (node (ref "R46") (pin "2") (pinfunction "2_2") (pintype "passive"))
      (node (ref "U2") (pin "53") (pinfunction "PC7/SEG16/ADC_IN6/SPI2_SSN_53") (pintype "passive"))
      (node (ref "U3") (pin "3") (pinfunction "SDA_3") (pintype "passive"))
    )
    (net (code "25") (name "/IO1") (class "Default")
      (node (ref "R45") (pin "2") (pinfunction "2_2") (pintype "passive"))
      (node (ref "U2") (pin "39") (pinfunction "PE3/SEG39/SPI0_MOSI_39") (pintype "passive"))
    )
    (net (code "26") (name "/IO2") (class "Default")
      (node (ref "R48") (pin "2") (pinfunction "2_2") (pintype "passive"))
      (node (ref "U2") (pin "41") (pinfunction "PC14/SEG41/U7816IO/LPT16_CH2_41") (pintype "passive"))
    )
    (net (code "27") (name "/IO3") (class "Default")
      (node (ref "R50") (pin "2") (pinfunction "2_2") (pintype "passive"))
      (node (ref "U2") (pin "42") (pinfunction "PC15/SEG42/LPT32_CH3/CAN_RX_42") (pintype "passive"))
    )
    (net (code "28") (name "/IO4") (class "Default")
      (node (ref "R52") (pin "2") (pinfunction "2_2") (pintype "passive"))
      (node (ref "U2") (pin "44") (pinfunction "PB15/VDISP0/SCL1/SPI2_MISO_44") (pintype "passive"))
    )
    (net (code "29") (name "/IO5") (class "Default")
      (node (ref "R53") (pin "2") (pinfunction "2_2") (pintype "passive"))
      (node (ref "U2") (pin "46") (pinfunction "PC0/VDISP2/GPT1_CH1/COMP3_INP1/LUT0_OUT_46") (pintype "passive"))
    )
    (net (code "30") (name "/IO6") (class "Default")
      (node (ref "R57") (pin "2") (pinfunction "2_2") (pintype "passive"))
      (node (ref "U2") (pin "48") (pinfunction "PC2/XTHIN/UART1_RX/LPUART1_RX_48") (pintype "passive"))
    )
    (net (code "31") (name "/IO7") (class "Default")
      (node (ref "R58") (pin "1") (pinfunction "1_1") (pintype "passive"))
      (node (ref "U2") (pin "36") (pinfunction "PE0/SEG36/SPI0_SSN_36") (pintype "passive"))
    )
    (net (code "32") (name "/IO8") (class "Default")
      (node (ref "R40") (pin "1") (pinfunction "1_1") (pintype "passive"))
      (node (ref "U2") (pin "38") (pinfunction "PE2/SEG38/SPI0_MISO_38") (pintype "passive"))
    )
    (net (code "33") (name "/IO9") (class "Default")
      (node (ref "R44") (pin "1") (pinfunction "1_1") (pintype "passive"))
      (node (ref "U2") (pin "40") (pinfunction "PC13/SEG40/U7816CLK/LPT16_CH1_40") (pintype "passive"))
    )
    (net (code "34") (name "/IO10") (class "Default")
      (node (ref "R47") (pin "1") (pinfunction "1_1") (pintype "passive"))
      (node (ref "U2") (pin "43") (pinfunction "PE5/SEG43/LPT32_CH4/CAN_TX_43") (pintype "passive"))
    )
    (net (code "35") (name "/IO11") (class "Default")
      (node (ref "R49") (pin "1") (pinfunction "1_1") (pintype "passive"))
      (node (ref "U2") (pin "45") (pinfunction "PD12/VDISP1/SDA1/SPI2_MOSI_45") (pintype "passive"))
    )
    (net (code "36") (name "/IO12") (class "Default")
      (node (ref "R51") (pin "1") (pinfunction "1_1") (pintype "passive"))
      (node (ref "U2") (pin "47") (pinfunction "PC1/VDISP3/GPT1_CH2/COMP3_INP2/LUT1_OUT_47") (pintype "passive"))
    )
    (net (code "37") (name "/IR_R") (class "Default")
      (node (ref "C1") (pin "1") (pinfunction "1_1") (pintype "passive"))
      (node (ref "Q8") (pin "3") (pinfunction "C_3") (pintype "passive"))
      (node (ref "R10") (pin "2") (pinfunction "2_2") (pintype "passive"))
      (node (ref "R31") (pin "2") (pinfunction "2_2") (pintype "passive"))
    )
    (net (code "38") (name "/IR_T") (class "Default")
      (node (ref "R18") (pin "1") (pinfunction "1_1") (pintype "passive"))
      (node (ref "R19") (pin "1") (pinfunction "1_1") (pintype "passive"))
      (node (ref "R30") (pin "2") (pinfunction "2_2") (pintype "passive"))
    )
    (net (code "39") (name "/KEY_OPEN") (class "Default")
      (node (ref "R38") (pin "2") (pinfunction "2_2") (pintype "passive"))
      (node (ref "U2") (pin "8") (pinfunction "PA2/COM2/UART0_RX/LPUART0_RX_8") (pintype "passive"))
    )
    (net (code "40") (name "/KEY_OPEN1") (class "Default")
      (node (ref "R39") (pin "2") (pinfunction "2_2") (pintype "passive"))
      (node (ref "U2") (pin "10") (pinfunction "PA4/COM4/SEG28/GPT1_CH3/COMP2_INN1_10") (pintype "passive"))
    )
    (net (code "41") (name "/LED") (class "Default")
      (node (ref "R68") (pin "1") (pinfunction "1_1") (pintype "passive"))
      (node (ref "U2") (pin "9") (pinfunction "PA3/COM3/UART0_TX/LPUART0_TX_9") (pintype "passive"))
    )
    (net (code "42") (name "/LED_IRQ_CTL") (class "Default")
      (node (ref "J2") (pin "16") (pinfunction "16_16") (pintype "passive"))
      (node (ref "U2") (pin "56") (pinfunction "PC10(WKUP5)/SEG19/ADC_IN15/SPI2_MOSI_56") (pintype "passive"))
    )
    (net (code "43") (name "/LED_TEST_Diode") (class "Default")
      (node (ref "P6") (pin "2") (pinfunction "2_2") (pintype "passive"))
      (node (ref "R88") (pin "2") (pinfunction "2_2") (pintype "passive"))
      (node (ref "R89") (pin "2") (pinfunction "2_2") (pintype "passive"))
      (node (ref "U2") (pin "70") (pinfunction "PD11(WKUP6)/FOUT0/ADC_IN0/ATIM_BRK1_70") (pintype "passive"))
    )
    (net (code "44") (name "/MOTO_B") (class "Default")
      (node (ref "J2") (pin "18") (pinfunction "18_18") (pintype "passive"))
      (node (ref "R21") (pin "2") (pinfunction "2_2") (pintype "passive"))
    )
    (net (code "45") (name "/MOTO_R") (class "Default")
      (node (ref "J2") (pin "20") (pinfunction "20_20") (pintype "passive"))
      (node (ref "R20") (pin "2") (pinfunction "2_2") (pintype "passive"))
    )
    (net (code "46") (name "/NB_PWRKEY") (class "Default")
      (node (ref "J2") (pin "15") (pinfunction "15_15") (pintype "passive"))
      (node (ref "U2") (pin "18") (pinfunction "PA12/SEG33/SDA0/LPUART2_TX_18") (pintype "passive"))
    )
    (net (code "47") (name "/NB_RST") (class "Default")
      (node (ref "J2") (pin "13") (pinfunction "13_13") (pintype "passive"))
      (node (ref "U2") (pin "14") (pinfunction "PA8/SEG0/LPT32_CH1/COMP2_INP1/SPI1_SSN_14") (pintype "passive"))
    )
    (net (code "48") (name "/NB_RXD") (class "Default")
      (node (ref "J2") (pin "11") (pinfunction "11_11") (pintype "passive"))
      (node (ref "R62") (pin "2") (pinfunction "2_2") (pintype "passive"))
    )
    (net (code "49") (name "/NB_TXD") (class "Default")
      (node (ref "J2") (pin "9") (pinfunction "9_9") (pintype "passive"))
      (node (ref "R61") (pin "2") (pinfunction "2_2") (pintype "passive"))
    )
    (net (code "50") (name "/PWM") (class "Default")
      (node (ref "P3") (pin "1") (pinfunction "1_1") (pintype "passive"))
      (node (ref "U2") (pin "25") (pinfunction "PB4/SEG3/ATIM_CH1/LPUART2_RX/COMP3_INN1_25") (pintype "passive"))
    )
    (net (code "51") (name "/RST_FM") (class "Default")
      (node (ref "R36") (pin "1") (pinfunction "1_1") (pintype "passive"))
      (node (ref "U2") (pin "80") (pinfunction "NRST_80") (pintype "passive"))
    )
    (net (code "52") (name "/SWCLK_FM") (class "Default")
      (node (ref "J1") (pin "2") (pinfunction "2_2") (pintype "passive"))
      (node (ref "R37") (pin "2") (pinfunction "2_2") (pintype "passive"))
      (node (ref "U2") (pin "78") (pinfunction "PD7/UART3_RX/SWCLK_78") (pintype "passive"))
    )
    (net (code "53") (name "/SWDIO_FM") (class "Default")
      (node (ref "J1") (pin "3") (pinfunction "3_3") (pintype "passive"))
      (node (ref "R43") (pin "2") (pinfunction "2_2") (pintype "passive"))
      (node (ref "U2") (pin "79") (pinfunction "PD8/UART3_TX/SWIO_79") (pintype "passive"))
    )
    (net (code "54") (name "/UART0_RXD") (class "Default")
      (node (ref "P5") (pin "2") (pinfunction "2_2") (pintype "passive"))
      (node (ref "R69") (pin "2") (pinfunction "2_2") (pintype "passive"))
      (node (ref "U2") (pin "3") (pinfunction "PA13/UART0_RX/LPUART0_RX/ADC_IN4_3") (pintype "passive"))
    )
    (net (code "55") (name "/UART0_TXD") (class "Default")
      (node (ref "P5") (pin "3") (pinfunction "3_3") (pintype "passive"))
      (node (ref "R67") (pin "2") (pinfunction "2_2") (pintype "passive"))
      (node (ref "U2") (pin "4") (pinfunction "PA14/UART0_TX/LPUART0_TX/ADC_IN11_4") (pintype "passive"))
    )
    (net (code "56") (name "/UART1_RXD") (class "Default")
      (node (ref "R31") (pin "1") (pinfunction "1_1") (pintype "passive"))
      (node (ref "U2") (pin "34") (pinfunction "PB13/SEG11/UART1_RX/LPUART1_RX_34") (pintype "passive"))
    )
    (net (code "57") (name "/UART1_TXD") (class "Default")
      (node (ref "R30") (pin "1") (pinfunction "1_1") (pintype "passive"))
      (node (ref "U2") (pin "35") (pinfunction "PB14/SEG12/UART1_TX/LPUART1_TX_35") (pintype "passive"))
    )
    (net (code "58") (name "/UART3_RXD") (class "Default")
      (node (ref "R61") (pin "1") (pinfunction "1_1") (pintype "passive"))
      (node (ref "U2") (pin "21") (pinfunction "PB0/SEG34/UART3_RX/SPI1_MISO/OPA1_OUT3_21") (pintype "passive"))
    )
    (net (code "59") (name "/UART3_TXD") (class "Default")
      (node (ref "R62") (pin "1") (pinfunction "1_1") (pintype "passive"))
      (node (ref "U2") (pin "22") (pinfunction "PB1/SEG35/UART3_TX/SPI1_MOSI/OPA1_OUT4_22") (pintype "passive"))
    )
    (net (code "60") (name "/UART4_RXD") (class "Default")
      (node (ref "R65") (pin "1") (pinfunction "1_1") (pintype "passive"))
      (node (ref "U2") (pin "6") (pinfunction "PA0/COM0/UART4_RX/ADC_IN5/LUT3_OUT_6") (pintype "passive"))
    )
    (net (code "61") (name "/UART4_TXD") (class "Default")
      (node (ref "R66") (pin "1") (pinfunction "1_1") (pintype "passive"))
      (node (ref "U2") (pin "7") (pinfunction "PA1/COM1/UART4_TX/ADC_IN12/LUT2_OUT_7") (pintype "passive"))
    )
    (net (code "62") (name "/UMU_RXD") (class "Default")
      (node (ref "J2") (pin "19") (pinfunction "19_19") (pintype "passive"))
      (node (ref "R66") (pin "2") (pinfunction "2_2") (pintype "passive"))
    )
    (net (code "63") (name "/UMU_TXD") (class "Default")
      (node (ref "J2") (pin "17") (pinfunction "17_17") (pintype "passive"))
      (node (ref "R65") (pin "2") (pinfunction "2_2") (pintype "passive"))
    )
    (net (code "64") (name "/UMU_WAKE") (class "Default")
      (node (ref "J2") (pin "14") (pinfunction "14_14") (pintype "passive"))
      (node (ref "R56") (pin "2") (pinfunction "2_2") (pintype "passive"))
      (node (ref "U2") (pin "23") (pinfunction "PB2(WKUP2)/VCIN1/UART4_RX/ATIM_CHIN_23") (pintype "passive"))
    )
    (net (code "65") (name "/Vout_3V6") (class "Default")
      (node (ref "Q12") (pin "2") (pinfunction "S_2") (pintype "passive"))
      (node (ref "R60") (pin "1") (pinfunction "1_1") (pintype "passive"))
      (node (ref "R63") (pin "2") (pinfunction "2_2") (pintype "passive"))
      (node (ref "R64") (pin "1") (pinfunction "1_1") (pintype "passive"))
    )
    (net (code "66") (name "/Vout_3V6_1") (class "Default")
      (node (ref "D2") (pin "2") (pinfunction "2_2") (pintype "passive"))
      (node (ref "J3") (pin "20") (pinfunction "20_20") (pintype "passive"))
    )
    (net (code "67") (name "/Vout_3V6_CHK") (class "Default")
      (node (ref "U2") (pin "72") (pinfunction "PD1/SEG23/UART5_TX/ADC_IN1/GPT2_CH2_72") (pintype "passive"))
    )
    (net (code "68") (name "/Vout_3V6_CTL") (class "Default")
      (node (ref "U2") (pin "30") (pinfunction "PB9/SEG8/SPI0_SCK/GPT0_ETR/COMP1_INP2_30") (pintype "passive"))
    )
    (net (code "69") (name "/Vout_7V2") (class "Default")
      (node (ref "Q10") (pin "2") (pinfunction "S_2") (pintype "passive"))
      (node (ref "R33") (pin "1") (pinfunction "1_1") (pintype "passive"))
      (node (ref "R34") (pin "2") (pinfunction "2_2") (pintype "passive"))
      (node (ref "R35") (pin "1") (pinfunction "1_1") (pintype "passive"))
    )
    (net (code "70") (name "/Vout_7V2_1") (class "Default")
      (node (ref "D1") (pin "2") (pinfunction "2_2") (pintype "passive"))
      (node (ref "J2") (pin "1") (pinfunction "1_1") (pintype "passive"))
    )
    (net (code "71") (name "/Vout_7V2_CHK") (class "Default")
      (node (ref "U2") (pin "71") (pinfunction "PD0/SEG22/UART5_RX/ADC_IN7/GPT2_CH1_71") (pintype "passive"))
    )
    (net (code "72") (name "/Vout_7V2_CTL") (class "Default")
      (node (ref "U2") (pin "31") (pinfunction "PB10/SEG9/SPI0_MISO/GPT0_CH1/OPA1_INN1_31") (pintype "passive"))
    )
    (net (code "73") (name "/XT1") (class "Default")
      (node (ref "C5") (pin "1") (pinfunction "1_1") (pintype "passive"))
      (node (ref "U2") (pin "61") (pinfunction "XT32KI_61") (pintype "passive"))
      (node (ref "Y1") (pin "1") (pinfunction "1_1") (pintype "passive"))
    )
    (net (code "74") (name "/XT2") (class "Default")
      (node (ref "C6") (pin "2") (pinfunction "2_2") (pintype "passive"))
      (node (ref "U2") (pin "60") (pinfunction "XT32KO_60") (pintype "passive"))
      (node (ref "Y1") (pin "2") (pinfunction "2_2") (pintype "passive"))
    )
    (net (code "75") (name "/gongwei1") (class "Default")
      (node (ref "P2") (pin "1") (pinfunction "1_1") (pintype "passive"))
      (node (ref "U2") (pin "29") (pinfunction "PB8/SEG7/SPI0_SSN/ATIM_CH3N/COMP1_INP1_29") (pintype "passive"))
    )
    (net (code "76") (name "/gongwei2") (class "Default")
      (node (ref "P2") (pin "3") (pinfunction "3_3") (pintype "passive"))
      (node (ref "U2") (pin "28") (pinfunction "PB7/SEG6/ATIM_CH4/SPI2_SCK/ANATST_28") (pintype "passive"))
    )
    (net (code "77") (name "/gongwei3") (class "Default")
      (node (ref "P2") (pin "5") (pinfunction "5_5") (pintype "passive"))
      (node (ref "U2") (pin "27") (pinfunction "PB6/SEG5/ATIM_CH3/SPI2_SSN_27") (pintype "passive"))
    )
    (net (code "78") (name "/gongwei4") (class "Default")
      (node (ref "P2") (pin "7") (pinfunction "7_7") (pintype "passive"))
      (node (ref "U2") (pin "26") (pinfunction "PB5/SEG4/ATIM_CH2/LPUART2_TX/COMP3_INN2_26") (pintype "passive"))
    )
    (net (code "79") (name "3.3V") (class "Default")
      (node (ref "C10") (pin "2") (pinfunction "2_2") (pintype "passive"))
      (node (ref "C2") (pin "2") (pinfunction "2_2") (pintype "passive"))
      (node (ref "C7") (pin "2") (pinfunction "2_2") (pintype "passive"))
      (node (ref "D3") (pin "1") (pinfunction "1_1") (pintype "passive"))
      (node (ref "J1") (pin "5") (pinfunction "5_5") (pintype "passive"))
      (node (ref "P1") (pin "1") (pinfunction "1_1") (pintype "passive"))
      (node (ref "P1") (pin "4") (pinfunction "4_4") (pintype "passive"))
      (node (ref "R10") (pin "1") (pinfunction "1_1") (pintype "passive"))
      (node (ref "R18") (pin "2") (pinfunction "2_2") (pintype "passive"))
      (node (ref "R22") (pin "1") (pinfunction "1_1") (pintype "passive"))
      (node (ref "R23") (pin "1") (pinfunction "1_1") (pintype "passive"))
      (node (ref "R37") (pin "1") (pinfunction "1_1") (pintype "passive"))
      (node (ref "R42") (pin "1") (pinfunction "1_1") (pintype "passive"))
      (node (ref "R43") (pin "1") (pinfunction "1_1") (pintype "passive"))
      (node (ref "R46") (pin "1") (pinfunction "1_1") (pintype "passive"))
      (node (ref "R88") (pin "1") (pinfunction "1_1") (pintype "passive"))
      (node (ref "U1") (pin "5") (pinfunction "Vs_5") (pintype "passive"))
      (node (ref "U2") (pin "64") (pinfunction "VDD(VDDA)_64") (pintype "passive"))
      (node (ref "U2") (pin "66") (pinfunction "VREFP_66") (pintype "passive"))
      (node (ref "U3") (pin "5") (pinfunction "Vs_5") (pintype "passive"))
    )
    (net (code "80") (name "12V") (class "Default")
      (node (ref "J3") (pin "17") (pinfunction "17_17") (pintype "passive"))
      (node (ref "J3") (pin "19") (pinfunction "19_19") (pintype "passive"))
    )
    (net (code "81") (name "GND") (class "Default")
      (node (ref "C1") (pin "2") (pinfunction "2_2") (pintype "passive"))
      (node (ref "C10") (pin "1") (pinfunction "1_1") (pintype "passive"))
      (node (ref "C2") (pin "1") (pinfunction "1_1") (pintype "passive"))
      (node (ref "C3") (pin "2") (pinfunction "2_2") (pintype "passive"))
      (node (ref "C5") (pin "2") (pinfunction "2_2") (pintype "passive"))
      (node (ref "C6") (pin "1") (pinfunction "1_1") (pintype "passive"))
      (node (ref "C7") (pin "1") (pinfunction "1_1") (pintype "passive"))
      (node (ref "C8") (pin "2") (pinfunction "2_2") (pintype "passive"))
      (node (ref "J1") (pin "4") (pinfunction "4_4") (pintype "passive"))
      (node (ref "J2") (pin "2") (pinfunction "2_2") (pintype "passive"))
      (node (ref "J3") (pin "1") (pinfunction "1_1") (pintype "passive"))
      (node (ref "J3") (pin "3") (pinfunction "3_3") (pintype "passive"))
      (node (ref "P2") (pin "2") (pinfunction "2_2") (pintype "passive"))
      (node (ref "P2") (pin "4") (pinfunction "4_4") (pintype "passive"))
      (node (ref "P2") (pin "6") (pinfunction "6_6") (pintype "passive"))
      (node (ref "P2") (pin "8") (pinfunction "8_8") (pintype "passive"))
      (node (ref "P3") (pin "3") (pinfunction "3_3") (pintype "passive"))
      (node (ref "P4") (pin "1") (pinfunction "1_1") (pintype "passive"))
      (node (ref "P5") (pin "1") (pinfunction "1_1") (pintype "passive"))
      (node (ref "P6") (pin "1") (pinfunction "1_1") (pintype "passive"))
      (node (ref "P7") (pin "5") (pinfunction "GND_5") (pintype "passive"))
      (node (ref "Q11") (pin "2") (pinfunction "E_2") (pintype "passive"))
      (node (ref "Q4") (pin "2") (pinfunction "E_2") (pintype "passive"))
      (node (ref "Q5") (pin "2") (pinfunction "E_2") (pintype "passive"))
      (node (ref "Q6") (pin "2") (pinfunction "E_2") (pintype "passive"))
      (node (ref "Q7") (pin "3") (pinfunction "C_3") (pintype "passive"))
      (node (ref "Q8") (pin "2") (pinfunction "E_2") (pintype "passive"))
      (node (ref "Q9") (pin "2") (pinfunction "E_2") (pintype "passive"))
      (node (ref "R11") (pin "2") (pinfunction "2_2") (pintype "passive"))
      (node (ref "R12") (pin "2") (pinfunction "2_2") (pintype "passive"))
      (node (ref "R13") (pin "2") (pinfunction "2_2") (pintype "passive"))
      (node (ref "R25") (pin "1") (pinfunction "1_1") (pintype "passive"))
      (node (ref "R26") (pin "1") (pinfunction "1_1") (pintype "passive"))
      (node (ref "R29") (pin "1") (pinfunction "1_1") (pintype "passive"))
      (node (ref "R56") (pin "1") (pinfunction "1_1") (pintype "passive"))
      (node (ref "R89") (pin "1") (pinfunction "1_1") (pintype "passive"))
      (node (ref "U1") (pin "1") (pinfunction "A1_1") (pintype "passive"))
      (node (ref "U1") (pin "2") (pinfunction "A0_2") (pintype "passive"))
      (node (ref "U1") (pin "6") (pinfunction "GND_6") (pintype "passive"))
      (node (ref "U2") (pin "63") (pinfunction "VSS(VSSA)_63") (pintype "passive"))
      (node (ref "U2") (pin "65") (pinfunction "VREFN_65") (pintype "passive"))
      (node (ref "U3") (pin "1") (pinfunction "A1_1") (pintype "passive"))
      (node (ref "U3") (pin "2") (pinfunction "A0_2") (pintype "passive"))
      (node (ref "U3") (pin "6") (pinfunction "GND_6") (pintype "passive"))
    )
    (net (code "82") (name "Net-(D3-Pad2)") (class "Default")
      (node (ref "D3") (pin "2") (pinfunction "2_2") (pintype "passive"))
      (node (ref "R68") (pin "2") (pinfunction "2_2") (pintype "passive"))
    )
    (net (code "83") (name "Net-(J1-Pad1)") (class "Default")
      (node (ref "J1") (pin "1") (pinfunction "1_1") (pintype "passive"))
      (node (ref "R36") (pin "2") (pinfunction "2_2") (pintype "passive"))
    )
    (net (code "84") (name "Net-(J3-Pad2)") (class "Default")
      (node (ref "J3") (pin "2") (pinfunction "2_2") (pintype "passive"))
      (node (ref "R38") (pin "1") (pinfunction "1_1") (pintype "passive"))
    )
    (net (code "85") (name "Net-(J3-Pad4)") (class "Default")
      (node (ref "J3") (pin "4") (pinfunction "4_4") (pintype "passive"))
      (node (ref "R39") (pin "1") (pinfunction "1_1") (pintype "passive"))
    )
    (net (code "86") (name "Net-(J3-Pad5)") (class "Default")
      (node (ref "J3") (pin "5") (pinfunction "5_5") (pintype "passive"))
      (node (ref "R58") (pin "2") (pinfunction "2_2") (pintype "passive"))
    )
    (net (code "87") (name "Net-(J3-Pad6)") (class "Default")
      (node (ref "J3") (pin "6") (pinfunction "6_6") (pintype "passive"))
      (node (ref "R41") (pin "1") (pinfunction "1_1") (pintype "passive"))
    )
    (net (code "88") (name "Net-(J3-Pad7)") (class "Default")
      (node (ref "J3") (pin "7") (pinfunction "7_7") (pintype "passive"))
      (node (ref "R40") (pin "2") (pinfunction "2_2") (pintype "passive"))
    )
    (net (code "89") (name "Net-(J3-Pad8)") (class "Default")
      (node (ref "J3") (pin "8") (pinfunction "8_8") (pintype "passive"))
      (node (ref "R45") (pin "1") (pinfunction "1_1") (pintype "passive"))
    )
    (net (code "90") (name "Net-(J3-Pad9)") (class "Default")
      (node (ref "J3") (pin "9") (pinfunction "9_9") (pintype "passive"))
      (node (ref "R44") (pin "2") (pinfunction "2_2") (pintype "passive"))
    )
    (net (code "91") (name "Net-(J3-Pad10)") (class "Default")
      (node (ref "J3") (pin "10") (pinfunction "10_10") (pintype "passive"))
      (node (ref "R48") (pin "1") (pinfunction "1_1") (pintype "passive"))
    )
    (net (code "92") (name "Net-(J3-Pad11)") (class "Default")
      (node (ref "J3") (pin "11") (pinfunction "11_11") (pintype "passive"))
      (node (ref "R47") (pin "2") (pinfunction "2_2") (pintype "passive"))
    )
    (net (code "93") (name "Net-(J3-Pad12)") (class "Default")
      (node (ref "J3") (pin "12") (pinfunction "12_12") (pintype "passive"))
      (node (ref "R50") (pin "1") (pinfunction "1_1") (pintype "passive"))
    )
    (net (code "94") (name "Net-(J3-Pad13)") (class "Default")
      (node (ref "J3") (pin "13") (pinfunction "13_13") (pintype "passive"))
      (node (ref "R49") (pin "2") (pinfunction "2_2") (pintype "passive"))
    )
    (net (code "95") (name "Net-(J3-Pad14)") (class "Default")
      (node (ref "J3") (pin "14") (pinfunction "14_14") (pintype "passive"))
      (node (ref "R52") (pin "1") (pinfunction "1_1") (pintype "passive"))
    )
    (net (code "96") (name "Net-(J3-Pad15)") (class "Default")
      (node (ref "J3") (pin "15") (pinfunction "15_15") (pintype "passive"))
      (node (ref "R51") (pin "2") (pinfunction "2_2") (pintype "passive"))
    )
    (net (code "97") (name "Net-(J3-Pad16)") (class "Default")
      (node (ref "J3") (pin "16") (pinfunction "16_16") (pintype "passive"))
      (node (ref "R53") (pin "1") (pinfunction "1_1") (pintype "passive"))
    )
    (net (code "98") (name "Net-(J3-Pad18)") (class "Default")
      (node (ref "J3") (pin "18") (pinfunction "18_18") (pintype "passive"))
      (node (ref "R57") (pin "1") (pinfunction "1_1") (pintype "passive"))
    )
    (net (code "99") (name "Net-(P1-Pad2)") (class "Default")
      (node (ref "P1") (pin "2") (pinfunction "2_2") (pintype "passive"))
      (node (ref "R17") (pin "2") (pinfunction "2_2") (pintype "passive"))
    )
    (net (code "100") (name "Net-(P1-Pad3)") (class "Default")
      (node (ref "P1") (pin "3") (pinfunction "3_3") (pintype "passive"))
      (node (ref "R24") (pin "2") (pinfunction "2_2") (pintype "passive"))
    )
    (net (code "101") (name "Net-(P4-Pad2)") (class "Default")
      (node (ref "P4") (pin "2") (pinfunction "2_2") (pintype "passive"))
      (node (ref "R69") (pin "1") (pinfunction "1_1") (pintype "passive"))
    )
    (net (code "102") (name "Net-(P4-Pad3)") (class "Default")
      (node (ref "P4") (pin "3") (pinfunction "3_3") (pintype "passive"))
      (node (ref "R67") (pin "1") (pinfunction "1_1") (pintype "passive"))
    )
    (net (code "103") (name "Net-(Q1-B)") (class "Default")
      (node (ref "Q1") (pin "1") (pinfunction "B_1") (pintype "passive"))
      (node (ref "R1") (pin "1") (pinfunction "1_1") (pintype "passive"))
      (node (ref "R7") (pin "1") (pinfunction "1_1") (pintype "passive"))
    )
    (net (code "104") (name "Net-(Q1-C)") (class "Default")
      (node (ref "Q1") (pin "3") (pinfunction "C_3") (pintype "passive"))
      (node (ref "R3") (pin "1") (pinfunction "1_1") (pintype "passive"))
    )
    (net (code "105") (name "Net-(Q2-B)") (class "Default")
      (node (ref "Q2") (pin "1") (pinfunction "B_1") (pintype "passive"))
      (node (ref "R2") (pin "1") (pinfunction "1_1") (pintype "passive"))
      (node (ref "R8") (pin "1") (pinfunction "1_1") (pintype "passive"))
    )
    (net (code "106") (name "Net-(Q2-C)") (class "Default")
      (node (ref "Q2") (pin "3") (pinfunction "C_3") (pintype "passive"))
      (node (ref "R4") (pin "1") (pinfunction "1_1") (pintype "passive"))
    )
    (net (code "107") (name "Net-(Q3-B)") (class "Default")
      (node (ref "Q3") (pin "1") (pinfunction "B_1") (pintype "passive"))
      (node (ref "R5") (pin "1") (pinfunction "1_1") (pintype "passive"))
      (node (ref "R9") (pin "1") (pinfunction "1_1") (pintype "passive"))
    )
    (net (code "108") (name "Net-(Q3-C)") (class "Default")
      (node (ref "Q3") (pin "3") (pinfunction "C_3") (pintype "passive"))
      (node (ref "R6") (pin "1") (pinfunction "1_1") (pintype "passive"))
    )
    (net (code "109") (name "Net-(Q4-B)") (class "Default")
      (node (ref "Q4") (pin "1") (pinfunction "B_1") (pintype "passive"))
      (node (ref "R14") (pin "2") (pinfunction "2_2") (pintype "passive"))
    )
    (net (code "110") (name "Net-(Q4-C)") (class "Default")
      (node (ref "Q4") (pin "3") (pinfunction "C_3") (pintype "passive"))
      (node (ref "R7") (pin "2") (pinfunction "2_2") (pintype "passive"))
    )
    (net (code "111") (name "Net-(Q5-B)") (class "Default")
      (node (ref "Q5") (pin "1") (pinfunction "B_1") (pintype "passive"))
      (node (ref "R15") (pin "2") (pinfunction "2_2") (pintype "passive"))
    )
    (net (code "112") (name "Net-(Q5-C)") (class "Default")
      (node (ref "Q5") (pin "3") (pinfunction "C_3") (pintype "passive"))
      (node (ref "R8") (pin "2") (pinfunction "2_2") (pintype "passive"))
    )
    (net (code "113") (name "Net-(Q6-B)") (class "Default")
      (node (ref "Q6") (pin "1") (pinfunction "B_1") (pintype "passive"))
      (node (ref "R16") (pin "2") (pinfunction "2_2") (pintype "passive"))
    )
    (net (code "114") (name "Net-(Q6-C)") (class "Default")
      (node (ref "Q6") (pin "3") (pinfunction "C_3") (pintype "passive"))
      (node (ref "R9") (pin "2") (pinfunction "2_2") (pintype "passive"))
    )
    (net (code "115") (name "Net-(Q7-B)") (class "Default")
      (node (ref "Q7") (pin "1") (pinfunction "B_1") (pintype "passive"))
      (node (ref "R19") (pin "2") (pinfunction "2_2") (pintype "passive"))
    )
    (net (code "116") (name "Net-(Q7-E)") (class "Default")
      (node (ref "Q7") (pin "2") (pinfunction "E_2") (pintype "passive"))
      (node (ref "R17") (pin "1") (pinfunction "1_1") (pintype "passive"))
    )
    (net (code "117") (name "Net-(Q8-B)") (class "Default")
      (node (ref "C3") (pin "1") (pinfunction "1_1") (pintype "passive"))
      (node (ref "Q8") (pin "1") (pinfunction "B_1") (pintype "passive"))
      (node (ref "R24") (pin "1") (pinfunction "1_1") (pintype "passive"))
      (node (ref "R29") (pin "2") (pinfunction "2_2") (pintype "passive"))
    )
    (net (code "118") (name "Net-(Q9-B)") (class "Default")
      (node (ref "Q9") (pin "1") (pinfunction "B_1") (pintype "passive"))
      (node (ref "R32") (pin "1") (pinfunction "1_1") (pintype "passive"))
    )
    (net (code "119") (name "Net-(Q9-C)") (class "Default")
      (node (ref "Q9") (pin "3") (pinfunction "C_3") (pintype "passive"))
      (node (ref "R28") (pin "2") (pinfunction "2_2") (pintype "passive"))
    )
    (net (code "120") (name "Net-(Q10-D)") (class "Default")
      (node (ref "D1") (pin "1") (pinfunction "1_1") (pintype "passive"))
      (node (ref "Q10") (pin "3") (pinfunction "D_3") (pintype "passive"))
      (node (ref "R27") (pin "1") (pinfunction "1_1") (pintype "passive"))
      (node (ref "R33") (pin "2") (pinfunction "2_2") (pintype "passive"))
    )
    (net (code "121") (name "Net-(Q10-G)") (class "Default")
      (node (ref "Q10") (pin "1") (pinfunction "G_1") (pintype "passive"))
      (node (ref "R28") (pin "1") (pinfunction "1_1") (pintype "passive"))
      (node (ref "R34") (pin "1") (pinfunction "1_1") (pintype "passive"))
    )
    (net (code "122") (name "Net-(Q11-B)") (class "Default")
      (node (ref "Q11") (pin "1") (pinfunction "B_1") (pintype "passive"))
      (node (ref "R59") (pin "1") (pinfunction "1_1") (pintype "passive"))
    )
    (net (code "123") (name "Net-(Q11-C)") (class "Default")
      (node (ref "Q11") (pin "3") (pinfunction "C_3") (pintype "passive"))
      (node (ref "R55") (pin "2") (pinfunction "2_2") (pintype "passive"))
    )
    (net (code "124") (name "Net-(Q12-D)") (class "Default")
      (node (ref "D2") (pin "1") (pinfunction "1_1") (pintype "passive"))
      (node (ref "Q12") (pin "3") (pinfunction "D_3") (pintype "passive"))
      (node (ref "R54") (pin "1") (pinfunction "1_1") (pintype "passive"))
      (node (ref "R60") (pin "2") (pinfunction "2_2") (pintype "passive"))
    )
    (net (code "125") (name "Net-(Q12-G)") (class "Default")
      (node (ref "Q12") (pin "1") (pinfunction "G_1") (pintype "passive"))
      (node (ref "R55") (pin "1") (pinfunction "1_1") (pintype "passive"))
      (node (ref "R63") (pin "1") (pinfunction "1_1") (pintype "passive"))
    )
    (net (code "126") (name "Net-(U1-Vin+)") (class "Default")
      (node (ref "C4") (pin "2") (pinfunction "2_2") (pintype "passive"))
      (node (ref "R35") (pin "2") (pinfunction "2_2") (pintype "passive"))
      (node (ref "U1") (pin "8") (pinfunction "Vin+_8") (pintype "passive"))
    )
    (net (code "127") (name "Net-(U1-Vin-)") (class "Default")
      (node (ref "C4") (pin "1") (pinfunction "1_1") (pintype "passive"))
      (node (ref "R27") (pin "2") (pinfunction "2_2") (pintype "passive"))
      (node (ref "U1") (pin "7") (pinfunction "Vin-_7") (pintype "passive"))
    )
    (net (code "128") (name "Net-(U2-VDD15)") (class "Default")
      (node (ref "C8") (pin "1") (pinfunction "1_1") (pintype "passive"))
      (node (ref "U2") (pin "62") (pinfunction "VDD15_62") (pintype "passive"))
    )
    (net (code "129") (name "Net-(U3-Vin+)") (class "Default")
      (node (ref "C9") (pin "2") (pinfunction "2_2") (pintype "passive"))
      (node (ref "R64") (pin "2") (pinfunction "2_2") (pintype "passive"))
      (node (ref "U3") (pin "8") (pinfunction "Vin+_8") (pintype "passive"))
    )
    (net (code "130") (name "Net-(U3-Vin-)") (class "Default")
      (node (ref "C9") (pin "1") (pinfunction "1_1") (pintype "passive"))
      (node (ref "R54") (pin "2") (pinfunction "2_2") (pintype "passive"))
      (node (ref "U3") (pin "7") (pinfunction "Vin-_7") (pintype "passive"))
    )
    (net (code "131") (name "VIN_5V") (class "Default")
      (node (ref "P3") (pin "2") (pinfunction "2_2") (pintype "passive"))
    )
    (net (code "132") (name "unconnected-(P4-Pad4)") (class "Default")
      (node (ref "P4") (pin "4") (pinfunction "4_4") (pintype "passive+no_connect"))
    )
    (net (code "133") (name "unconnected-(P5-Pad4)") (class "Default")
      (node (ref "P5") (pin "4") (pinfunction "4_4") (pintype "passive+no_connect"))
    )
    (net (code "134") (name "unconnected-(U2-PA5{slash}COM5{slash}SEG29{slash}GPT1_CH4{slash}COMP2_INN2-Pad11)") (class "Default")
      (node (ref "U2") (pin "11") (pinfunction "PA5/COM5/SEG29/GPT1_CH4/COMP2_INN2_11") (pintype "passive+no_connect"))
    )
    (net (code "135") (name "unconnected-(U2-PA6{slash}COM6{slash}SEG30{slash}OPA1_INN2{slash}CAN_RX-Pad12)") (class "Default")
      (node (ref "U2") (pin "12") (pinfunction "PA6/COM6/SEG30/OPA1_INN2/CAN_RX_12") (pintype "passive+no_connect"))
    )
    (net (code "136") (name "unconnected-(U2-PA7{slash}COM7{slash}SEG31{slash}OPA1_INP2{slash}CAN_TX-Pad13)") (class "Default")
      (node (ref "U2") (pin "13") (pinfunction "PA7/COM7/SEG31/OPA1_INP2/CAN_TX_13") (pintype "passive+no_connect"))
    )
    (net (code "137") (name "unconnected-(U2-PA11{slash}SEG32{slash}SCL0{slash}LPUART2_RX-Pad17)") (class "Default")
      (node (ref "U2") (pin "17") (pinfunction "PA11/SEG32/SCL0/LPUART2_RX_17") (pintype "passive+no_connect"))
    )
    (net (code "138") (name "unconnected-(U2-PA15{slash}WKUP0{slash}SVS{slash}COMP3_OUT-Pad5)") (class "Default")
      (node (ref "U2") (pin "5") (pinfunction "PA15/WKUP0/SVS/COMP3_OUT_5") (pintype "passive+no_connect"))
    )
    (net (code "139") (name "unconnected-(U2-PB3{slash}VCIN2{slash}UART4_TX{slash}ATIM_CH2N-Pad24)") (class "Default")
      (node (ref "U2") (pin "24") (pinfunction "PB3/VCIN2/UART4_TX/ATIM_CH2N_24") (pintype "passive+no_connect"))
    )
    (net (code "140") (name "unconnected-(U2-PB12(WKUP3){slash}ATIM_ETR{slash}FOUT1{slash}OPA1_OUT1-Pad33)") (class "Default")
      (node (ref "U2") (pin "33") (pinfunction "PB12(WKUP3)/ATIM_ETR/FOUT1/OPA1_OUT1_33") (pintype "passive+no_connect"))
    )
    (net (code "141") (name "unconnected-(U2-PC11{slash}SEG20{slash}U7816CLK{slash}GPTO_CH3{slash}ADC_IN16-Pad57)") (class "Default")
      (node (ref "U2") (pin "57") (pinfunction "PC11/SEG20/U7816CLK/GPTO_CH3/ADC_IN16_57") (pintype "passive+no_connect"))
    )
    (net (code "142") (name "unconnected-(U2-PC12{slash}SEG21{slash}U7816IO{slash}GPTO_CH4{slash}ADC_IN17-Pad58)") (class "Default")
      (node (ref "U2") (pin "58") (pinfunction "PC12/SEG21/U7816IO/GPTO_CH4/ADC_IN17_58") (pintype "passive+no_connect"))
    )
    (net (code "143") (name "unconnected-(U2-PD9(WKUP8)-Pad19)") (class "Default")
      (node (ref "U2") (pin "19") (pinfunction "PD9(WKUP8)_19") (pintype "passive+no_connect"))
    )
    (net (code "144") (name "unconnected-(U2-PD10{slash}CAN_RX{slash}ADC_IN18-Pad1)") (class "Default")
      (node (ref "U2") (pin "1") (pinfunction "PD10/CAN_RX/ADC_IN18_1") (pintype "passive+no_connect"))
    )
    (net (code "145") (name "unconnected-(U2-PE6(WKUP9)-Pad68)") (class "Default")
      (node (ref "U2") (pin "68") (pinfunction "PE6(WKUP9)_68") (pintype "passive+no_connect"))
    )
    (net (code "146") (name "unconnected-(U2-PE7{slash}COMP3_OUT-Pad69)") (class "Default")
      (node (ref "U2") (pin "69") (pinfunction "PE7/COMP3_OUT_69") (pintype "passive+no_connect"))
    )
    (net (code "147") (name "unconnected-(U2-PE8-Pad20)") (class "Default")
      (node (ref "U2") (pin "20") (pinfunction "PE8_20") (pintype "passive+no_connect"))
    )
    (net (code "148") (name "unconnected-(U2-PE9{slash}CAN_TX{slash}ADC_IN19-Pad2)") (class "Default")
      (node (ref "U2") (pin "2") (pinfunction "PE9/CAN_TX/ADC_IN19_2") (pintype "passive+no_connect"))
    )
    (net (code "149") (name "unconnected-(U2-PH15{slash}RTCOUT{slash}TAMPER-Pad59)") (class "Default")
      (node (ref "U2") (pin "59") (pinfunction "PH15/RTCOUT/TAMPER_59") (pintype "passive+no_connect"))
    )
    (net (code "150") (name "unconnected-(U2-VBAT-Pad67)") (class "Default")
      (node (ref "U2") (pin "67") (pinfunction "VBAT_67") (pintype "passive+no_connect"))
    )
  )
)
